# IPNS_v0_1_STIM.net
KiCad netlist of a schematic drawn in EAGLE
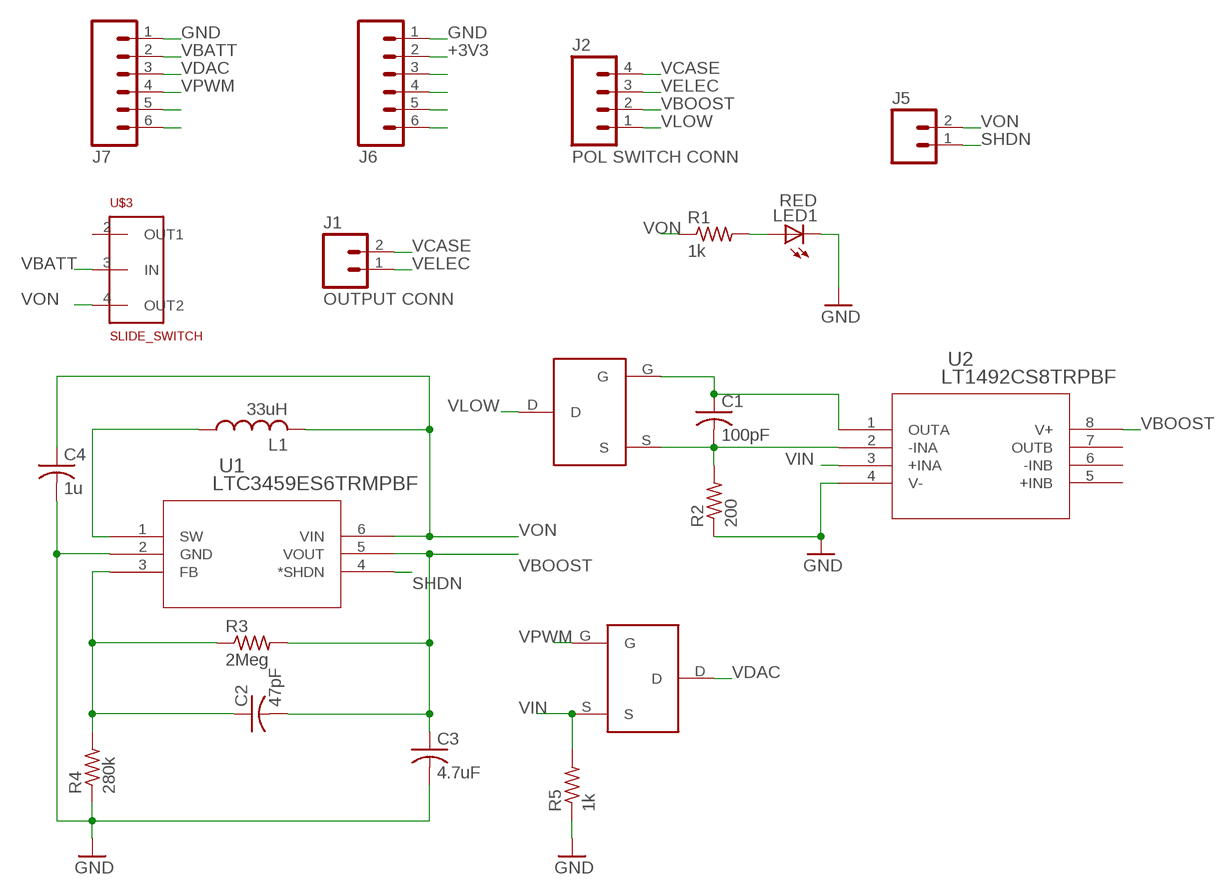
[diagram p0: schematic, sheet 1]

(export (version "E")
  (design (tool "Eeschema 10.0.6"))
  (components
    (comp (ref "C1")
      (value "100pF")
      (footprint "eagle-import:C0805")
      (libsource (lib "eagle-import") (part "C-USC0805"))
    )
    (comp (ref "C2")
      (value "47pF")
      (footprint "eagle-import:C0805")
      (libsource (lib "eagle-import") (part "C-USC0805"))
    )
    (comp (ref "C3")
      (value "4.7uF")
      (footprint "eagle-import:C0805")
      (libsource (lib "eagle-import") (part "C-USC0805"))
    )
    (comp (ref "C4")
      (value "1u")
      (footprint "eagle-import:C0805")
      (libsource (lib "eagle-import") (part "C-USC0805"))
    )
    (comp (ref "J1")
      (value "OUTPUT CONN")
      (footprint "eagle-import:1X02")
      (libsource (lib "eagle-import") (part "M02PTH"))
    )
    (comp (ref "J2")
      (value "POL SWITCH CONN")
      (footprint "eagle-import:1X04")
      (libsource (lib "eagle-import") (part "M04PTH"))
    )
    (comp (ref "J5")
      (value "M02PTH")
      (footprint "eagle-import:1X02")
      (libsource (lib "eagle-import") (part "M02PTH"))
    )
    (comp (ref "J6")
      (value "M06SILK_FEMALE_PTH")
      (footprint "eagle-import:1X06")
      (libsource (lib "eagle-import") (part "M06SILK_FEMALE_PTH"))
    )
    (comp (ref "J7")
      (value "M06SILK_FEMALE_PTH")
      (footprint "eagle-import:1X06")
      (libsource (lib "eagle-import") (part "M06SILK_FEMALE_PTH"))
    )
    (comp (ref "L1")
      (value "33uH")
      (footprint "eagle-import:L2012C")
      (libsource (lib "eagle-import") (part "L-USL2012C"))
    )
    (comp (ref "LED1")
      (value "RED")
      (footprint "eagle-import:CHIP-LED0805")
      (libsource (lib "eagle-import") (part "LEDCHIP-LED0805"))
    )
    (comp (ref "R1")
      (value "1k")
      (footprint "eagle-import:M0805")
      (libsource (lib "eagle-import") (part "R-US_M0805"))
    )
    (comp (ref "R2")
      (value "200")
      (footprint "eagle-import:R0805")
      (libsource (lib "eagle-import") (part "R-US_R0805"))
    )
    (comp (ref "R3")
      (value "2Meg")
      (footprint "eagle-import:R0805")
      (libsource (lib "eagle-import") (part "R-US_R0805"))
    )
    (comp (ref "R4")
      (value "280k")
      (footprint "eagle-import:R0805")
      (libsource (lib "eagle-import") (part "R-US_R0805"))
    )
    (comp (ref "R5")
      (value "1k")
      (footprint "eagle-import:R0805")
      (libsource (lib "eagle-import") (part "R-US_R0805"))
    )
    (comp (ref "U$1")
      (value "DMN1019USN")
      (footprint "eagle-import:DMN1019USN")
      (libsource (lib "eagle-import") (part "DMN1019USN"))
    )
    (comp (ref "U$2")
      (value "DMN1019USN")
      (footprint "eagle-import:DMN1019USN")
      (libsource (lib "eagle-import") (part "DMN1019USN"))
    )
    (comp (ref "U$3")
      (value "SLIDE_SWITCH")
      (footprint "eagle-import:SLIDE_SWITCH")
      (libsource (lib "eagle-import") (part "SLIDE_SWITCH"))
    )
    (comp (ref "U1")
      (value "LTC3459ES6TRMPBF")
      (footprint "eagle-import:TSOT-23_S6")
      (fields
        (field (name "MANUFACTURER_PART_NUMBER") "ltc3459es6#trmpbf")
        (field (name "COPYRIGHT") "Copyright (C) 2016 Accelerated Designs. All rights reserved")
      )
      (libsource (lib "eagle-import") (part "LTC3459ES6TRMPBF"))
    )
    (comp (ref "U2")
      (value "LT1492CS8TRPBF")
      (footprint "eagle-import:SO-8_S")
      (fields (field (name "MANUFACTURER_PART_NUMBER") "lt1492cs8#trpbf"))
      (libsource (lib "eagle-import") (part "LT1492CS8TRPBF"))
    )
  )
  (nets
    (net (code "1") (name "/+3V3") (class "Default")
      (node (ref "J6") (pin "2") (pinfunction "2_2") (pintype "passive"))
    )
    (net (code "2") (name "/SHDN") (class "Default")
      (node (ref "J5") (pin "1") (pinfunction "1_1") (pintype "passive"))
      (node (ref "U1") (pin "4") (pinfunction "*SHDN_4") (pintype "input"))
    )
    (net (code "3") (name "/VBATT") (class "Default")
      (node (ref "J7") (pin "2") (pinfunction "2_2") (pintype "passive"))
      (node (ref "U$3") (pin "3") (pinfunction "IN_3") (pintype "bidirectional"))
    )
    (net (code "4") (name "/VBOOST") (class "Default")
      (node (ref "C2") (pin "2") (pinfunction "2_2") (pintype "passive"))
      (node (ref "C3") (pin "1") (pinfunction "1_1") (pintype "passive"))
      (node (ref "J2") (pin "2") (pinfunction "2_2") (pintype "passive"))
      (node (ref "R3") (pin "2") (pinfunction "2_2") (pintype "passive"))
      (node (ref "U1") (pin "5") (pinfunction "VOUT_5") (pintype "output"))
      (node (ref "U2") (pin "8") (pinfunction "V+_8") (pintype "power_in"))
    )
    (net (code "5") (name "/VCASE") (class "Default")
      (node (ref "J1") (pin "2") (pinfunction "2_2") (pintype "passive"))
      (node (ref "J2") (pin "4") (pinfunction "4_4") (pintype "passive"))
    )
    (net (code "6") (name "/VDAC") (class "Default")
      (node (ref "J7") (pin "3") (pinfunction "3_3") (pintype "passive"))
      (node (ref "U$2") (pin "D") (pinfunction "D_D") (pintype "bidirectional"))
    )
    (net (code "7") (name "/VELEC") (class "Default")
      (node (ref "J1") (pin "1") (pinfunction "1_1") (pintype "passive"))
      (node (ref "J2") (pin "3") (pinfunction "3_3") (pintype "passive"))
    )
    (net (code "8") (name "/VIN") (class "Default")
      (node (ref "R5") (pin "2") (pinfunction "2_2") (pintype "passive"))
      (node (ref "U$2") (pin "S") (pinfunction "S_S") (pintype "bidirectional"))
      (node (ref "U2") (pin "3") (pinfunction "+INA_3") (pintype "input"))
    )
    (net (code "9") (name "/VLOW") (class "Default")
      (node (ref "J2") (pin "1") (pinfunction "1_1") (pintype "passive"))
      (node (ref "U$1") (pin "D") (pinfunction "D_D") (pintype "bidirectional"))
    )
    (net (code "10") (name "/VON") (class "Default")
      (node (ref "C4") (pin "1") (pinfunction "1_1") (pintype "passive"))
      (node (ref "J5") (pin "2") (pinfunction "2_2") (pintype "passive"))
      (node (ref "L1") (pin "2") (pinfunction "2_2") (pintype "passive"))
      (node (ref "R1") (pin "1") (pinfunction "1_1") (pintype "passive"))
      (node (ref "U$3") (pin "4") (pinfunction "OUT2_4") (pintype "bidirectional"))
      (node (ref "U1") (pin "6") (pinfunction "VIN_6") (pintype "input"))
    )
    (net (code "11") (name "/VPWM") (class "Default")
      (node (ref "J7") (pin "4") (pinfunction "4_4") (pintype "passive"))
      (node (ref "U$2") (pin "G") (pinfunction "G_G") (pintype "bidirectional"))
    )
    (net (code "12") (name "GND") (class "Default")
      (node (ref "C3") (pin "2") (pinfunction "2_2") (pintype "passive"))
      (node (ref "C4") (pin "2") (pinfunction "2_2") (pintype "passive"))
      (node (ref "J6") (pin "1") (pinfunction "1_1") (pintype "passive"))
      (node (ref "J7") (pin "1") (pinfunction "1_1") (pintype "passive"))
      (node (ref "LED1") (pin "C") (pinfunction "C_C") (pintype "passive"))
      (node (ref "R2") (pin "1") (pinfunction "1_1") (pintype "passive"))
      (node (ref "R4") (pin "1") (pinfunction "1_1") (pintype "passive"))
      (node (ref "R5") (pin "1") (pinfunction "1_1") (pintype "passive"))
      (node (ref "U1") (pin "2") (pinfunction "GND_2") (pintype "power_in"))
      (node (ref "U2") (pin "4") (pinfunction "V-_4") (pintype "power_in"))
    )
    (net (code "13") (name "Net-(LED1-PadA)") (class "Default")
      (node (ref "LED1") (pin "A") (pinfunction "A_A") (pintype "passive"))
      (node (ref "R1") (pin "2") (pinfunction "2_2") (pintype "passive"))
    )
    (net (code "14") (name "Net-(U1-FB)") (class "Default")
      (node (ref "C2") (pin "1") (pinfunction "1_1") (pintype "passive"))
      (node (ref "R3") (pin "1") (pinfunction "1_1") (pintype "passive"))
      (node (ref "R4") (pin "2") (pinfunction "2_2") (pintype "passive"))
      (node (ref "U1") (pin "3") (pinfunction "FB_3") (pintype "input"))
    )
    (net (code "15") (name "Net-(U1-SW)") (class "Default")
      (node (ref "L1") (pin "1") (pinfunction "1_1") (pintype "passive"))
      (node (ref "U1") (pin "1") (pinfunction "SW_1") (pintype "passive"))
    )
    (net (code "16") (name "Net-(U2--INA)") (class "Default")
      (node (ref "C1") (pin "2") (pinfunction "2_2") (pintype "passive"))
      (node (ref "R2") (pin "2") (pinfunction "2_2") (pintype "passive"))
      (node (ref "U$1") (pin "S") (pinfunction "S_S") (pintype "bidirectional"))
      (node (ref "U2") (pin "2") (pinfunction "-INA_2") (pintype "input"))
    )
    (net (code "17") (name "Net-(U2-OUTA)") (class "Default")
      (node (ref "C1") (pin "1") (pinfunction "1_1") (pintype "passive"))
      (node (ref "U$1") (pin "G") (pinfunction "G_G") (pintype "bidirectional"))
      (node (ref "U2") (pin "1") (pinfunction "OUTA_1") (pintype "output"))
    )
    (net (code "18") (name "unconnected-(J6-Pad3)") (class "Default")
      (node (ref "J6") (pin "3") (pinfunction "3_3") (pintype "passive"))
    )
    (net (code "19") (name "unconnected-(J6-Pad4)") (class "Default")
      (node (ref "J6") (pin "4") (pinfunction "4_4") (pintype "passive"))
    )
    (net (code "20") (name "unconnected-(J6-Pad5)") (class "Default")
      (node (ref "J6") (pin "5") (pinfunction "5_5") (pintype "passive"))
    )
    (net (code "21") (name "unconnected-(J6-Pad6)") (class "Default")
      (node (ref "J6") (pin "6") (pinfunction "6_6") (pintype "passive"))
    )
    (net (code "22") (name "unconnected-(J7-Pad5)") (class "Default")
      (node (ref "J7") (pin "5") (pinfunction "5_5") (pintype "passive"))
    )
    (net (code "23") (name "unconnected-(J7-Pad6)") (class "Default")
      (node (ref "J7") (pin "6") (pinfunction "6_6") (pintype "passive"))
    )
    (net (code "24") (name "unconnected-(U$3-OUT1-Pad2)") (class "Default")
      (node (ref "U$3") (pin "2") (pinfunction "OUT1_2") (pintype "bidirectional"))
    )
    (net (code "25") (name "unconnected-(U2-+INB-Pad5)") (class "Default")
      (node (ref "U2") (pin "5") (pinfunction "+INB_5") (pintype "input"))
    )
    (net (code "26") (name "unconnected-(U2--INB-Pad6)") (class "Default")
      (node (ref "U2") (pin "6") (pinfunction "-INB_6") (pintype "input"))
    )
    (net (code "27") (name "unconnected-(U2-OUTB-Pad7)") (class "Default")
      (node (ref "U2") (pin "7") (pinfunction "OUTB_7") (pintype "output"))
    )
  )
)
